# MP3Player.net
KiCad netlist of a schematic drawn in Altium Designer
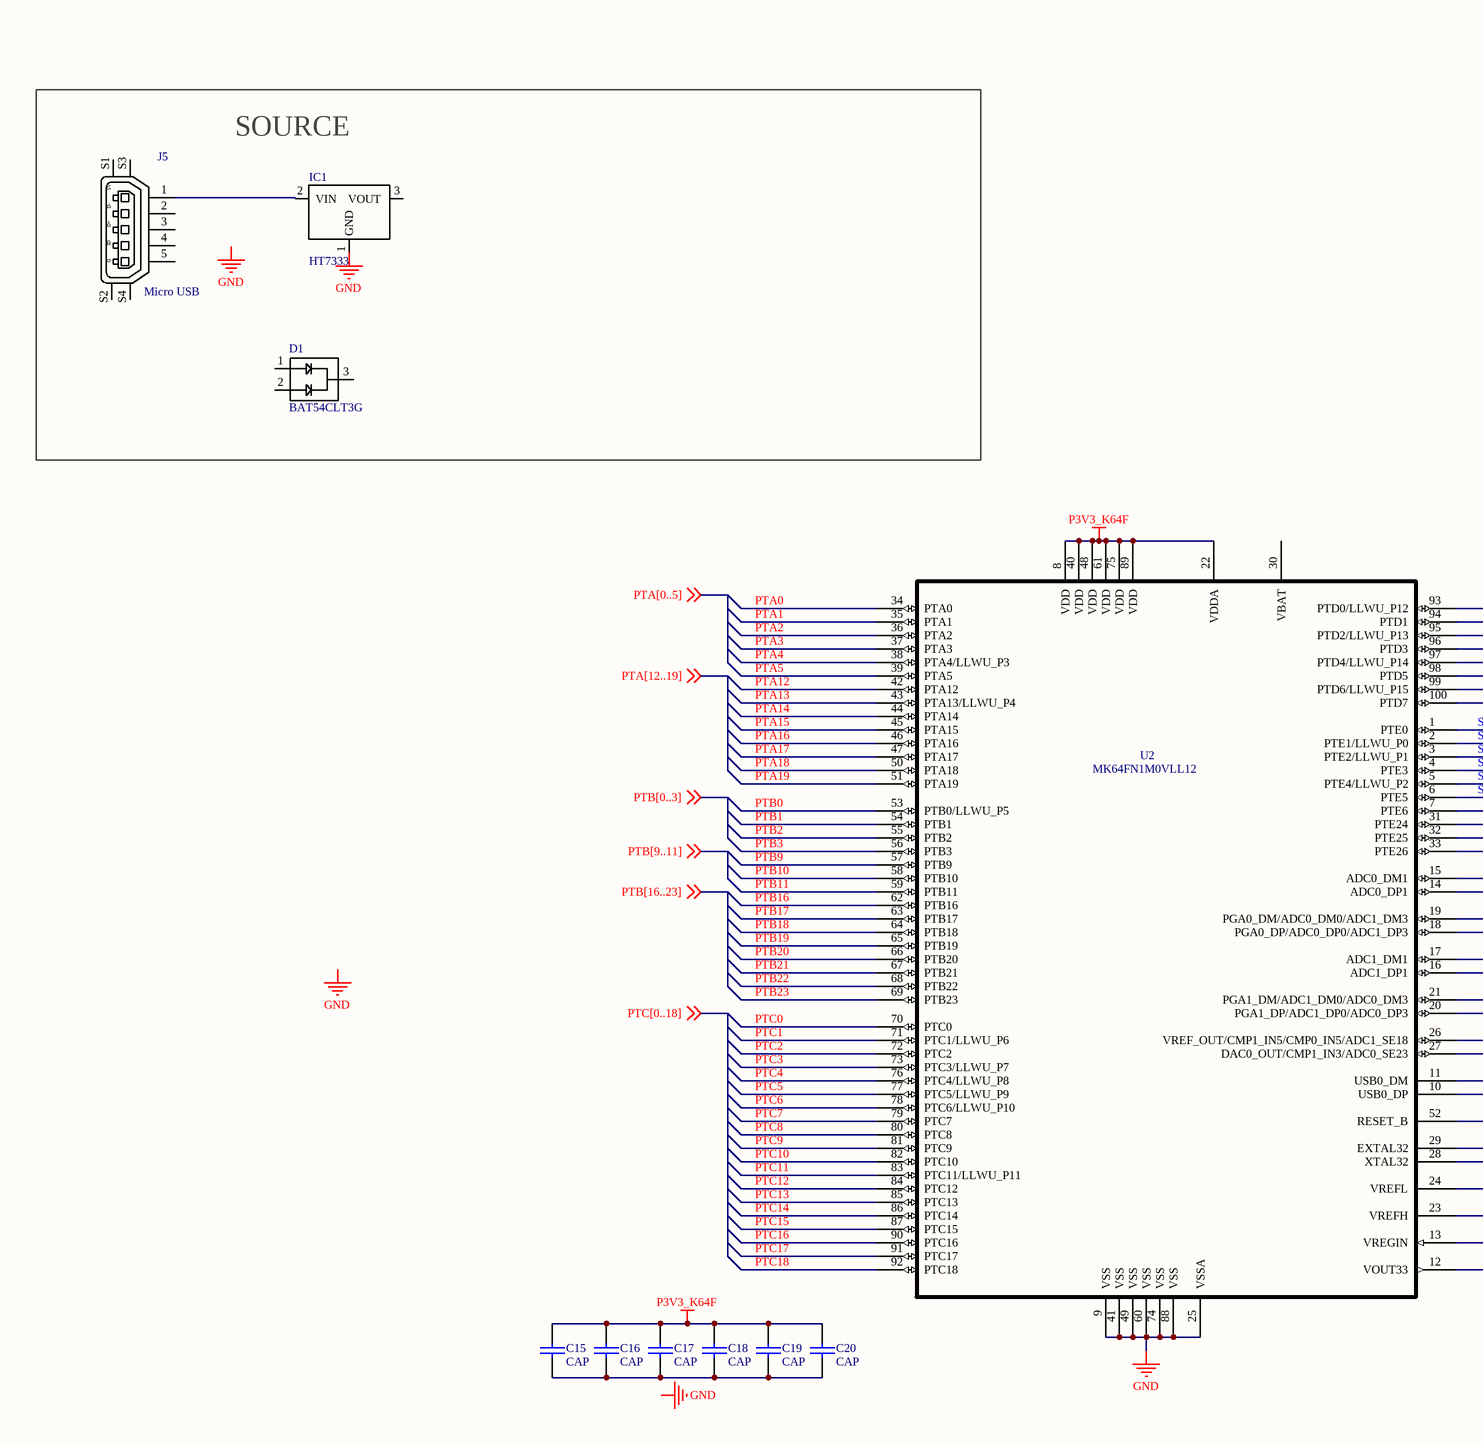
[diagram p0: MP3Player.SchDoc, left]
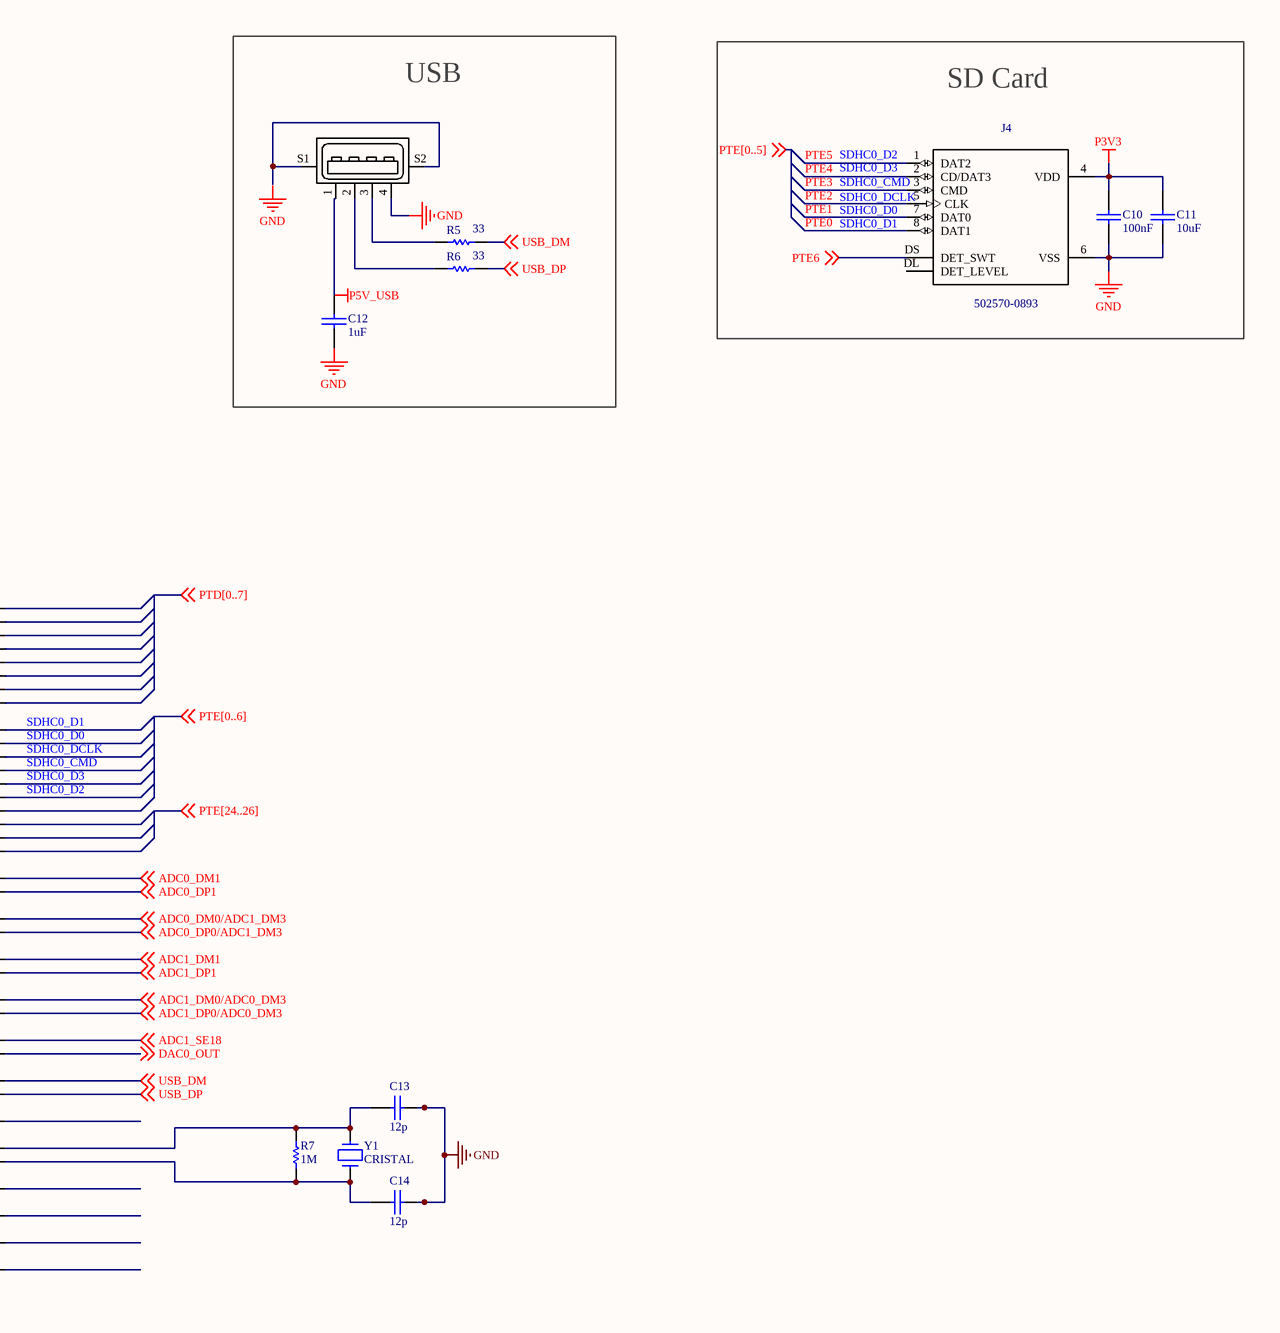
[diagram p1: MP3Player.SchDoc, right]

(export (version "E")
  (design (tool "Eeschema 10.0.6"))
  (components
    (comp (ref "C10") (value "100nF") (footprint "0805") (libsource (lib "LIBEBAL") (part "CAP")))
    (comp (ref "C11") (value "10uF") (footprint "0805") (libsource (lib "LIBEBAL") (part "CAP")))
    (comp (ref "C12") (value "1uF") (footprint "0805") (libsource (lib "LIBEBAL") (part "CAP")))
    (comp (ref "C13") (value "12p") (footprint "0805") (libsource (lib "LIBEBAL") (part "CAP")))
    (comp (ref "C14") (value "12p") (footprint "0805") (libsource (lib "LIBEBAL") (part "CAP")))
    (comp (ref "C15") (value "CAP") (footprint "0805") (libsource (lib "LIBEBAL") (part "CAP")))
    (comp (ref "C16") (value "CAP") (footprint "0805") (libsource (lib "LIBEBAL") (part "CAP")))
    (comp (ref "C17") (value "CAP") (footprint "0805") (libsource (lib "LIBEBAL") (part "CAP")))
    (comp (ref "C18") (value "CAP") (footprint "0805") (libsource (lib "LIBEBAL") (part "CAP")))
    (comp (ref "C19") (value "CAP") (footprint "0805") (libsource (lib "LIBEBAL") (part "CAP")))
    (comp (ref "C20") (value "CAP") (footprint "0805") (libsource (lib "LIBEBAL") (part "CAP")))
    (comp (ref "D1")
      (value "BAT54CLT3G")
      (footprint "SOT96P237X111-3N")
      (fields (field (name "MOUSER PART NUMBER") "863-BAT54CLT3G"))
      (libsource (lib "BAT54CLT3G") (part "BAT54CLT3G"))
    )
    (comp (ref "IC1")
      (value "HT7333")
      (description "Micropower Voltage  Regulator")
      (libsource (lib "Ht7333") (part "HT7333"))
    )
    (comp (ref "J3")
      (value "UJ2-AH-1-SMT")
      (footprint "CUI_UJ2-AH-1-SMT_UJ2-AH-1-SMT(Primary)")
      (description "Standard A type 4 pin Horizontal 3 Âµin Plating SMT USB 2.0 Jack")
      (fields (field (name "MP") "UJ2-AH-1-SMT-TR") (field (name "MF") "CUI Inc."))
      (libsource (lib "USB-A-SMT") (part "UJ2-AH-1-SMT"))
    )
    (comp (ref "J4")
      (value "502570-0893")
      (footprint "MOLEX_502570-0893_502570-0893(Primary)")
      (description "1.10mm Pitch microSD Memory Card Connector, Normal Mount Surface Mount, Push-Push Type")
      (fields (field (name "MF") "Molex"))
      (libsource (lib "MicroSD") (part "502570-0893"))
    )
    (comp (ref "J5")
      (value "Micro USB")
      (footprint "HRS_ZX62D-B-5P8_ZX62D-B-5P8(Primary)")
      (description "SMD+DIP Micro USB; MICRO-B-SMD")
      (fields (field (name "MF") "Hirose") (field (name "MP") "ZX62D-B-5P8"))
      (libsource (lib "MicroUSB-B-5") (part "ZX62D-B-5P8"))
    )
    (comp (ref "R5") (value "33") (footprint "0805") (libsource (lib "LIBEBAL") (part "RES")))
    (comp (ref "R6") (value "33") (footprint "0805") (libsource (lib "LIBEBAL") (part "RES")))
    (comp (ref "R7") (value "1M") (footprint "RES400") (libsource (lib "LIBEBAL") (part "RES")))
    (comp (ref "U2")
      (value "MK64FN1M0VLL12")
      (footprint "LQFP-100_14X14X1")
      (description "Imported")
      (fields (field (name "MANUFACTURER_PART_NUMBER") "mk64fn1m0vll12"))
      (libsource (lib "MK64FN1M0VLL12") (part "MK64FN1M0VLL12"))
    )
    (comp (ref "Y1")
      (value "CRISTAL")
      (footprint "CRISTAL PERFIL")
      (libsource (lib "LIBEBAL") (part "CRISTAL"))
    )
  )
  (nets
    (net (code "1") (name "ADC0_DM0{slash}ADC1_DM3") (class "Default")
      (node (ref "U2") (pin "19") (pinfunction "PGA0_DM/ADC0_DM0/ADC1_DM3_19") (pintype "bidirectional"))
    )
    (net (code "2") (name "ADC0_DM1") (class "Default")
      (node (ref "U2") (pin "15") (pinfunction "ADC0_DM1_15") (pintype "bidirectional"))
    )
    (net (code "3") (name "ADC0_DP0{slash}ADC1_DM3") (class "Default")
      (node (ref "U2") (pin "18") (pinfunction "PGA0_DP/ADC0_DP0/ADC1_DP3_18") (pintype "bidirectional"))
    )
    (net (code "4") (name "ADC0_DP1") (class "Default")
      (node (ref "U2") (pin "14") (pinfunction "ADC0_DP1_14") (pintype "bidirectional"))
    )
    (net (code "5") (name "ADC1_DM0{slash}ADC0_DM3") (class "Default")
      (node (ref "U2") (pin "21") (pinfunction "PGA1_DM/ADC1_DM0/ADC0_DM3_21") (pintype "bidirectional"))
    )
    (net (code "6") (name "ADC1_DM1") (class "Default")
      (node (ref "U2") (pin "17") (pinfunction "ADC1_DM1_17") (pintype "bidirectional"))
    )
    (net (code "7") (name "ADC1_DP0{slash}ADC0_DM3") (class "Default")
      (node (ref "U2") (pin "20") (pinfunction "PGA1_DP/ADC1_DP0/ADC0_DP3_20") (pintype "bidirectional"))
    )
    (net (code "8") (name "ADC1_DP1") (class "Default")
      (node (ref "U2") (pin "16") (pinfunction "ADC1_DP1_16") (pintype "bidirectional"))
    )
    (net (code "9") (name "ADC1_SE18") (class "Default")
      (node (ref "U2") (pin "26") (pinfunction "VREF_OUT/CMP1_IN5/CMP0_IN5/ADC1_SE18_26") (pintype "bidirectional"))
    )
    (net (code "10") (name "DAC0_OUT") (class "Default")
      (node (ref "U2") (pin "27") (pinfunction "DAC0_OUT/CMP1_IN3/ADC0_SE23_27") (pintype "bidirectional"))
    )
    (net (code "11") (name "GND") (class "Default")
      (node (ref "C10") (pin "2") (pinfunction "2_2") (pintype "passive"))
      (node (ref "C11") (pin "2") (pinfunction "2_2") (pintype "passive"))
      (node (ref "C12") (pin "2") (pinfunction "2_2") (pintype "passive"))
      (node (ref "C13") (pin "2") (pinfunction "2_2") (pintype "passive"))
      (node (ref "C14") (pin "2") (pinfunction "2_2") (pintype "passive"))
      (node (ref "IC1") (pin "1") (pinfunction "GND_1") (pintype "passive"))
      (node (ref "J3") (pin "4") (pinfunction "4_4") (pintype "passive"))
      (node (ref "J4") (pin "6") (pinfunction "VSS_6") (pintype "power_in"))
      (node (ref "U2") (pin "25") (pinfunction "VSSA_25") (pintype "power_in"))
      (node (ref "U2") (pin "41") (pinfunction "VSS_41") (pintype "power_in"))
      (node (ref "U2") (pin "49") (pinfunction "VSS_49") (pintype "power_in"))
      (node (ref "U2") (pin "60") (pinfunction "VSS_60") (pintype "power_in"))
      (node (ref "U2") (pin "74") (pinfunction "VSS_74") (pintype "power_in"))
      (node (ref "U2") (pin "88") (pinfunction "VSS_88") (pintype "power_in"))
      (node (ref "U2") (pin "9") (pinfunction "VSS_9") (pintype "power_in"))
    )
    (net (code "12") (name "Net-(C12-Pad1)") (class "Default")
      (node (ref "C12") (pin "1") (pinfunction "1_1") (pintype "passive"))
      (node (ref "J3") (pin "1") (pinfunction "1_1") (pintype "passive"))
    )
    (net (code "13") (name "Net-(C15-Pad2)") (class "Default")
      (node (ref "C15") (pin "2") (pinfunction "2_2") (pintype "passive"))
      (node (ref "C16") (pin "2") (pinfunction "2_2") (pintype "passive"))
      (node (ref "C17") (pin "2") (pinfunction "2_2") (pintype "passive"))
      (node (ref "C18") (pin "2") (pinfunction "2_2") (pintype "passive"))
      (node (ref "C19") (pin "2") (pinfunction "2_2") (pintype "passive"))
      (node (ref "C20") (pin "2") (pinfunction "2_2") (pintype "passive"))
    )
    (net (code "14") (name "Net-(IC1-VIN)") (class "Default")
      (node (ref "IC1") (pin "2") (pinfunction "VIN_2") (pintype "passive"))
      (node (ref "J5") (pin "1") (pinfunction "1_1") (pintype "passive"))
    )
    (net (code "15") (name "Net-(J3-Pad2)") (class "Default")
      (node (ref "J3") (pin "2") (pinfunction "2_2") (pintype "passive"))
      (node (ref "R6") (pin "2") (pinfunction "2_2") (pintype "passive"))
    )
    (net (code "16") (name "Net-(J3-Pad3)") (class "Default")
      (node (ref "J3") (pin "3") (pinfunction "3_3") (pintype "passive"))
      (node (ref "R5") (pin "2") (pinfunction "2_2") (pintype "passive"))
    )
    (net (code "17") (name "Net-(J3-SHIELD-PadS1)") (class "Default")
      (node (ref "J3") (pin "S1") (pinfunction "SHIELD_S1") (pintype "passive"))
      (node (ref "J3") (pin "S2") (pinfunction "SHIELD_S2") (pintype "passive"))
    )
    (net (code "18") (name "Net-(U2-EXTAL32)") (class "Default")
      (node (ref "C13") (pin "1") (pinfunction "1_1") (pintype "passive"))
      (node (ref "R7") (pin "2") (pinfunction "2_2") (pintype "passive"))
      (node (ref "U2") (pin "29") (pinfunction "EXTAL32_29") (pintype "passive"))
      (node (ref "Y1") (pin "2") (pinfunction "10_2") (pintype "passive"))
    )
    (net (code "19") (name "Net-(U2-XTAL32)") (class "Default")
      (node (ref "C14") (pin "1") (pinfunction "1_1") (pintype "passive"))
      (node (ref "R7") (pin "1") (pinfunction "1_1") (pintype "passive"))
      (node (ref "U2") (pin "28") (pinfunction "XTAL32_28") (pintype "passive"))
      (node (ref "Y1") (pin "1") (pinfunction "1_1") (pintype "passive"))
    )
    (net (code "20") (name "P3V3") (class "Default")
      (node (ref "C10") (pin "1") (pinfunction "1_1") (pintype "passive"))
      (node (ref "C11") (pin "1") (pinfunction "1_1") (pintype "passive"))
      (node (ref "J4") (pin "4") (pinfunction "VDD_4") (pintype "power_in"))
    )
    (net (code "21") (name "P3V3_K64F") (class "Default")
      (node (ref "C15") (pin "1") (pinfunction "1_1") (pintype "passive"))
      (node (ref "C16") (pin "1") (pinfunction "1_1") (pintype "passive"))
      (node (ref "C17") (pin "1") (pinfunction "1_1") (pintype "passive"))
      (node (ref "C18") (pin "1") (pinfunction "1_1") (pintype "passive"))
      (node (ref "C19") (pin "1") (pinfunction "1_1") (pintype "passive"))
      (node (ref "C20") (pin "1") (pinfunction "1_1") (pintype "passive"))
      (node (ref "U2") (pin "22") (pinfunction "VDDA_22") (pintype "power_in"))
      (node (ref "U2") (pin "40") (pinfunction "VDD_40") (pintype "power_in"))
      (node (ref "U2") (pin "48") (pinfunction "VDD_48") (pintype "power_in"))
      (node (ref "U2") (pin "61") (pinfunction "VDD_61") (pintype "power_in"))
      (node (ref "U2") (pin "75") (pinfunction "VDD_75") (pintype "power_in"))
      (node (ref "U2") (pin "8") (pinfunction "VDD_8") (pintype "power_in"))
      (node (ref "U2") (pin "89") (pinfunction "VDD_89") (pintype "power_in"))
    )
    (net (code "23") (name "PTA0") (class "Default")
      (node (ref "U2") (pin "34") (pinfunction "PTA0_34") (pintype "bidirectional"))
    )
    (net (code "24") (name "PTA1") (class "Default")
      (node (ref "U2") (pin "35") (pinfunction "PTA1_35") (pintype "bidirectional"))
    )
    (net (code "25") (name "PTA2") (class "Default")
      (node (ref "U2") (pin "36") (pinfunction "PTA2_36") (pintype "bidirectional"))
    )
    (net (code "26") (name "PTA3") (class "Default")
      (node (ref "U2") (pin "37") (pinfunction "PTA3_37") (pintype "bidirectional"))
    )
    (net (code "27") (name "PTA4") (class "Default")
      (node (ref "U2") (pin "38") (pinfunction "PTA4/LLWU_P3_38") (pintype "bidirectional"))
    )
    (net (code "28") (name "PTA5") (class "Default")
      (node (ref "U2") (pin "39") (pinfunction "PTA5_39") (pintype "bidirectional"))
    )
    (net (code "29") (name "PTA12") (class "Default")
      (node (ref "U2") (pin "42") (pinfunction "PTA12_42") (pintype "bidirectional"))
    )
    (net (code "30") (name "PTA13") (class "Default")
      (node (ref "U2") (pin "43") (pinfunction "PTA13/LLWU_P4_43") (pintype "bidirectional"))
    )
    (net (code "31") (name "PTA14") (class "Default")
      (node (ref "U2") (pin "44") (pinfunction "PTA14_44") (pintype "bidirectional"))
    )
    (net (code "32") (name "PTA15") (class "Default")
      (node (ref "U2") (pin "45") (pinfunction "PTA15_45") (pintype "bidirectional"))
    )
    (net (code "33") (name "PTA16") (class "Default")
      (node (ref "U2") (pin "46") (pinfunction "PTA16_46") (pintype "bidirectional"))
    )
    (net (code "34") (name "PTA17") (class "Default")
      (node (ref "U2") (pin "47") (pinfunction "PTA17_47") (pintype "bidirectional"))
    )
    (net (code "35") (name "PTA18") (class "Default")
      (node (ref "U2") (pin "50") (pinfunction "PTA18_50") (pintype "bidirectional"))
    )
    (net (code "36") (name "PTA19") (class "Default")
      (node (ref "U2") (pin "51") (pinfunction "PTA19_51") (pintype "bidirectional"))
    )
    (net (code "39") (name "PTB0") (class "Default")
      (node (ref "U2") (pin "53") (pinfunction "PTB0/LLWU_P5_53") (pintype "bidirectional"))
    )
    (net (code "40") (name "PTB1") (class "Default")
      (node (ref "U2") (pin "54") (pinfunction "PTB1_54") (pintype "bidirectional"))
    )
    (net (code "41") (name "PTB2") (class "Default")
      (node (ref "U2") (pin "55") (pinfunction "PTB2_55") (pintype "bidirectional"))
    )
    (net (code "42") (name "PTB3") (class "Default")
      (node (ref "U2") (pin "56") (pinfunction "PTB3_56") (pintype "bidirectional"))
    )
    (net (code "43") (name "PTB9") (class "Default")
      (node (ref "U2") (pin "57") (pinfunction "PTB9_57") (pintype "bidirectional"))
    )
    (net (code "44") (name "PTB10") (class "Default")
      (node (ref "U2") (pin "58") (pinfunction "PTB10_58") (pintype "bidirectional"))
    )
    (net (code "45") (name "PTB11") (class "Default")
      (node (ref "U2") (pin "59") (pinfunction "PTB11_59") (pintype "bidirectional"))
    )
    (net (code "46") (name "PTB16") (class "Default")
      (node (ref "U2") (pin "62") (pinfunction "PTB16_62") (pintype "bidirectional"))
    )
    (net (code "47") (name "PTB17") (class "Default")
      (node (ref "U2") (pin "63") (pinfunction "PTB17_63") (pintype "bidirectional"))
    )
    (net (code "48") (name "PTB18") (class "Default")
      (node (ref "U2") (pin "64") (pinfunction "PTB18_64") (pintype "bidirectional"))
    )
    (net (code "49") (name "PTB19") (class "Default")
      (node (ref "U2") (pin "65") (pinfunction "PTB19_65") (pintype "bidirectional"))
    )
    (net (code "50") (name "PTB20") (class "Default")
      (node (ref "U2") (pin "66") (pinfunction "PTB20_66") (pintype "bidirectional"))
    )
    (net (code "51") (name "PTB21") (class "Default")
      (node (ref "U2") (pin "67") (pinfunction "PTB21_67") (pintype "bidirectional"))
    )
    (net (code "52") (name "PTB22") (class "Default")
      (node (ref "U2") (pin "68") (pinfunction "PTB22_68") (pintype "bidirectional"))
    )
    (net (code "53") (name "PTB23") (class "Default")
      (node (ref "U2") (pin "69") (pinfunction "PTB23_69") (pintype "bidirectional"))
    )
    (net (code "57") (name "PTC0") (class "Default")
      (node (ref "U2") (pin "70") (pinfunction "PTC0_70") (pintype "bidirectional"))
    )
    (net (code "58") (name "PTC1") (class "Default")
      (node (ref "U2") (pin "71") (pinfunction "PTC1/LLWU_P6_71") (pintype "bidirectional"))
    )
    (net (code "59") (name "PTC2") (class "Default")
      (node (ref "U2") (pin "72") (pinfunction "PTC2_72") (pintype "bidirectional"))
    )
    (net (code "60") (name "PTC3") (class "Default")
      (node (ref "U2") (pin "73") (pinfunction "PTC3/LLWU_P7_73") (pintype "bidirectional"))
    )
    (net (code "61") (name "PTC4") (class "Default")
      (node (ref "U2") (pin "76") (pinfunction "PTC4/LLWU_P8_76") (pintype "bidirectional"))
    )
    (net (code "62") (name "PTC5") (class "Default")
      (node (ref "U2") (pin "77") (pinfunction "PTC5/LLWU_P9_77") (pintype "bidirectional"))
    )
    (net (code "63") (name "PTC6") (class "Default")
      (node (ref "U2") (pin "78") (pinfunction "PTC6/LLWU_P10_78") (pintype "bidirectional"))
    )
    (net (code "64") (name "PTC7") (class "Default")
      (node (ref "U2") (pin "79") (pinfunction "PTC7_79") (pintype "bidirectional"))
    )
    (net (code "65") (name "PTC8") (class "Default")
      (node (ref "U2") (pin "80") (pinfunction "PTC8_80") (pintype "bidirectional"))
    )
    (net (code "66") (name "PTC9") (class "Default")
      (node (ref "U2") (pin "81") (pinfunction "PTC9_81") (pintype "bidirectional"))
    )
    (net (code "67") (name "PTC10") (class "Default")
      (node (ref "U2") (pin "82") (pinfunction "PTC10_82") (pintype "bidirectional"))
    )
    (net (code "68") (name "PTC11") (class "Default")
      (node (ref "U2") (pin "83") (pinfunction "PTC11/LLWU_P11_83") (pintype "bidirectional"))
    )
    (net (code "69") (name "PTC12") (class "Default")
      (node (ref "U2") (pin "84") (pinfunction "PTC12_84") (pintype "bidirectional"))
    )
    (net (code "70") (name "PTC13") (class "Default")
      (node (ref "U2") (pin "85") (pinfunction "PTC13_85") (pintype "bidirectional"))
    )
    (net (code "71") (name "PTC14") (class "Default")
      (node (ref "U2") (pin "86") (pinfunction "PTC14_86") (pintype "bidirectional"))
    )
    (net (code "72") (name "PTC15") (class "Default")
      (node (ref "U2") (pin "87") (pinfunction "PTC15_87") (pintype "bidirectional"))
    )
    (net (code "73") (name "PTC16") (class "Default")
      (node (ref "U2") (pin "90") (pinfunction "PTC16_90") (pintype "bidirectional"))
    )
    (net (code "74") (name "PTC17") (class "Default")
      (node (ref "U2") (pin "91") (pinfunction "PTC17_91") (pintype "bidirectional"))
    )
    (net (code "75") (name "PTC18") (class "Default")
      (node (ref "U2") (pin "92") (pinfunction "PTC18_92") (pintype "bidirectional"))
    )
    (net (code "78") (name "PTE0") (class "Default")
      (node (ref "J4") (pin "8") (pinfunction "DAT1_8") (pintype "bidirectional"))
    )
    (net (code "79") (name "PTE1") (class "Default")
      (node (ref "J4") (pin "7") (pinfunction "DAT0_7") (pintype "bidirectional"))
    )
    (net (code "80") (name "PTE2") (class "Default")
      (node (ref "J4") (pin "5") (pinfunction "CLK_5") (pintype "input"))
    )
    (net (code "81") (name "PTE3") (class "Default")
      (node (ref "J4") (pin "3") (pinfunction "CMD_3") (pintype "bidirectional"))
    )
    (net (code "82") (name "PTE4") (class "Default")
      (node (ref "J4") (pin "2") (pinfunction "CD/DAT3_2") (pintype "bidirectional"))
    )
    (net (code "83") (name "PTE5") (class "Default")
      (node (ref "J4") (pin "1") (pinfunction "DAT2_1") (pintype "bidirectional"))
    )
    (net (code "84") (name "PTE6") (class "Default")
      (node (ref "J4") (pin "DS") (pinfunction "DET_SWT_DS") (pintype "passive"))
    )
    (net (code "88") (name "USB_DM") (class "Default")
      (node (ref "R5") (pin "1") (pinfunction "1_1") (pintype "passive"))
      (node (ref "U2") (pin "11") (pinfunction "USB0_DM_11") (pintype "passive"))
    )
    (net (code "89") (name "USB_DP") (class "Default")
      (node (ref "R6") (pin "1") (pinfunction "1_1") (pintype "passive"))
      (node (ref "U2") (pin "10") (pinfunction "USB0_DP_10") (pintype "passive"))
    )
    (net (code "90") (name "unconnected-(D1-A1-Pad1)") (class "Default")
      (node (ref "D1") (pin "1") (pinfunction "A1_1") (pintype "passive"))
    )
    (net (code "91") (name "unconnected-(D1-A2-Pad2)") (class "Default")
      (node (ref "D1") (pin "2") (pinfunction "A2_2") (pintype "passive"))
    )
    (net (code "92") (name "unconnected-(D1-K-Pad3)") (class "Default")
      (node (ref "D1") (pin "3") (pinfunction "K_3") (pintype "passive"))
    )
    (net (code "93") (name "unconnected-(IC1-VOUT-Pad3)") (class "Default")
      (node (ref "IC1") (pin "3") (pinfunction "VOUT_3") (pintype "passive"))
    )
    (net (code "94") (name "unconnected-(J4-DET_LEVEL-PadDL)") (class "Default")
      (node (ref "J4") (pin "DL") (pinfunction "DET_LEVEL_DL") (pintype "passive"))
    )
    (net (code "95") (name "unconnected-(J5-Pad2)") (class "Default")
      (node (ref "J5") (pin "2") (pinfunction "2_2") (pintype "passive"))
    )
    (net (code "96") (name "unconnected-(J5-Pad3)") (class "Default")
      (node (ref "J5") (pin "3") (pinfunction "3_3") (pintype "passive"))
    )
    (net (code "97") (name "unconnected-(J5-Pad4)") (class "Default")
      (node (ref "J5") (pin "4") (pinfunction "4_4") (pintype "passive"))
    )
    (net (code "98") (name "unconnected-(J5-Pad5)") (class "Default")
      (node (ref "J5") (pin "5") (pinfunction "5_5") (pintype "passive"))
    )
    (net (code "99") (name "unconnected-(J5-SHIELD-PadS1)") (class "Default")
      (node (ref "J5") (pin "S1") (pinfunction "SHIELD_S1") (pintype "passive"))
    )
    (net (code "100") (name "unconnected-(J5-SHIELD-PadS2)") (class "Default")
      (node (ref "J5") (pin "S2") (pinfunction "SHIELD_S2") (pintype "passive"))
    )
    (net (code "101") (name "unconnected-(J5-SHIELD-PadS3)") (class "Default")
      (node (ref "J5") (pin "S3") (pinfunction "SHIELD_S3") (pintype "passive"))
    )
    (net (code "102") (name "unconnected-(J5-SHIELD-PadS4)") (class "Default")
      (node (ref "J5") (pin "S4") (pinfunction "SHIELD_S4") (pintype "passive"))
    )
    (net (code "103") (name "unconnected-(U2-PTD0{slash}LLWU_P12-Pad93)") (class "Default")
      (node (ref "U2") (pin "93") (pinfunction "PTD0/LLWU_P12_93") (pintype "bidirectional"))
    )
    (net (code "104") (name "unconnected-(U2-PTD1-Pad94)") (class "Default")
      (node (ref "U2") (pin "94") (pinfunction "PTD1_94") (pintype "bidirectional"))
    )
    (net (code "105") (name "unconnected-(U2-PTD2{slash}LLWU_P13-Pad95)") (class "Default")
      (node (ref "U2") (pin "95") (pinfunction "PTD2/LLWU_P13_95") (pintype "bidirectional"))
    )
    (net (code "106") (name "unconnected-(U2-PTD3-Pad96)") (class "Default")
      (node (ref "U2") (pin "96") (pinfunction "PTD3_96") (pintype "bidirectional"))
    )
    (net (code "107") (name "unconnected-(U2-PTD4{slash}LLWU_P14-Pad97)") (class "Default")
      (node (ref "U2") (pin "97") (pinfunction "PTD4/LLWU_P14_97") (pintype "bidirectional"))
    )
    (net (code "108") (name "unconnected-(U2-PTD5-Pad98)") (class "Default")
      (node (ref "U2") (pin "98") (pinfunction "PTD5_98") (pintype "bidirectional"))
    )
    (net (code "109") (name "unconnected-(U2-PTD6{slash}LLWU_P15-Pad99)") (class "Default")
      (node (ref "U2") (pin "99") (pinfunction "PTD6/LLWU_P15_99") (pintype "bidirectional"))
    )
    (net (code "110") (name "unconnected-(U2-PTD7-Pad100)") (class "Default")
      (node (ref "U2") (pin "100") (pinfunction "PTD7_100") (pintype "bidirectional"))
    )
    (net (code "111") (name "unconnected-(U2-PTE0-Pad1)") (class "Default")
      (node (ref "U2") (pin "1") (pinfunction "PTE0_1") (pintype "bidirectional"))
    )
    (net (code "112") (name "unconnected-(U2-PTE1{slash}LLWU_P0-Pad2)") (class "Default")
      (node (ref "U2") (pin "2") (pinfunction "PTE1/LLWU_P0_2") (pintype "bidirectional"))
    )
    (net (code "113") (name "unconnected-(U2-PTE2{slash}LLWU_P1-Pad3)") (class "Default")
      (node (ref "U2") (pin "3") (pinfunction "PTE2/LLWU_P1_3") (pintype "bidirectional"))
    )
    (net (code "114") (name "unconnected-(U2-PTE3-Pad4)") (class "Default")
      (node (ref "U2") (pin "4") (pinfunction "PTE3_4") (pintype "bidirectional"))
    )
    (net (code "115") (name "unconnected-(U2-PTE4{slash}LLWU_P2-Pad5)") (class "Default")
      (node (ref "U2") (pin "5") (pinfunction "PTE4/LLWU_P2_5") (pintype "bidirectional"))
    )
    (net (code "116") (name "unconnected-(U2-PTE5-Pad6)") (class "Default")
      (node (ref "U2") (pin "6") (pinfunction "PTE5_6") (pintype "bidirectional"))
    )
    (net (code "117") (name "unconnected-(U2-PTE6-Pad7)") (class "Default")
      (node (ref "U2") (pin "7") (pinfunction "PTE6_7") (pintype "bidirectional"))
    )
    (net (code "118") (name "unconnected-(U2-PTE24-Pad31)") (class "Default")
      (node (ref "U2") (pin "31") (pinfunction "PTE24_31") (pintype "bidirectional"))
    )
    (net (code "119") (name "unconnected-(U2-PTE25-Pad32)") (class "Default")
      (node (ref "U2") (pin "32") (pinfunction "PTE25_32") (pintype "bidirectional"))
    )
    (net (code "120") (name "unconnected-(U2-PTE26-Pad33)") (class "Default")
      (node (ref "U2") (pin "33") (pinfunction "PTE26_33") (pintype "bidirectional"))
    )
    (net (code "121") (name "unconnected-(U2-RESET_B-Pad52)") (class "Default")
      (node (ref "U2") (pin "52") (pinfunction "RESET_B_52") (pintype "passive"))
    )
    (net (code "122") (name "unconnected-(U2-VBAT-Pad30)") (class "Default")
      (node (ref "U2") (pin "30") (pinfunction "VBAT_30") (pintype "power_in"))
    )
    (net (code "123") (name "unconnected-(U2-VOUT33-Pad12)") (class "Default")
      (node (ref "U2") (pin "12") (pinfunction "VOUT33_12") (pintype "output"))
    )
    (net (code "124") (name "unconnected-(U2-VREFH-Pad23)") (class "Default")
      (node (ref "U2") (pin "23") (pinfunction "VREFH_23") (pintype "power_in"))
    )
    (net (code "125") (name "unconnected-(U2-VREFL-Pad24)") (class "Default")
      (node (ref "U2") (pin "24") (pinfunction "VREFL_24") (pintype "power_in"))
    )
    (net (code "126") (name "unconnected-(U2-VREGIN-Pad13)") (class "Default")
      (node (ref "U2") (pin "13") (pinfunction "VREGIN_13") (pintype "input"))
    )
  )
)
